# vcf.net
KiCad netlist of a schematic drawn in EAGLE
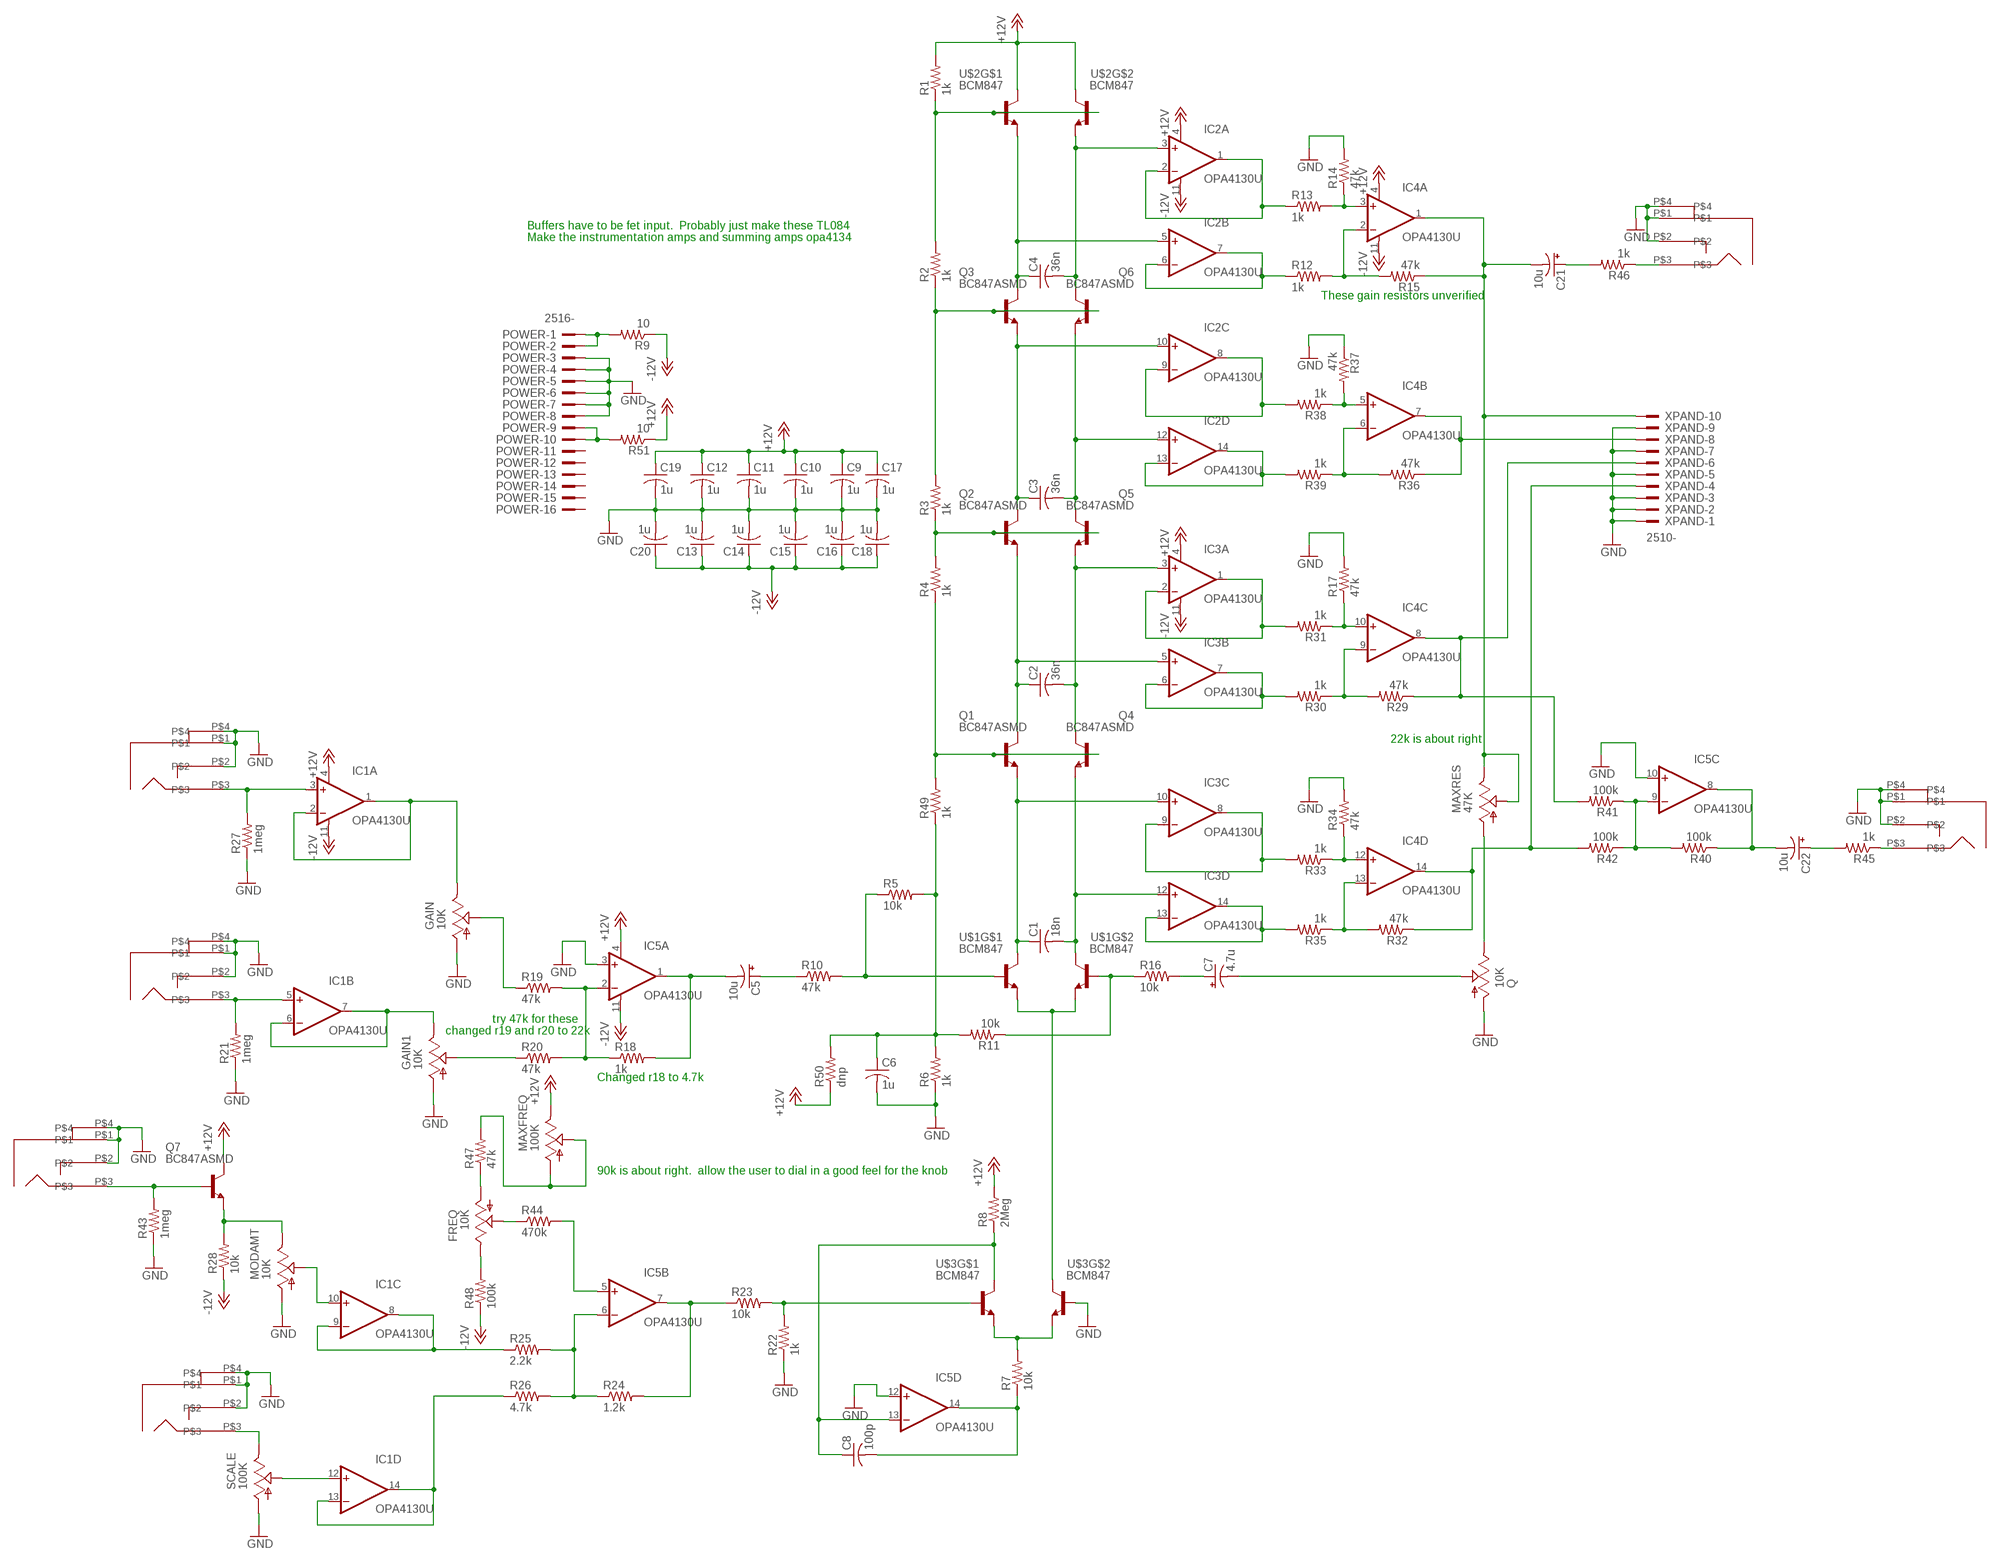
[diagram p0: schematic, sheet 1]

(export (version "E")
  (design (tool "Eeschema 10.0.6"))
  (components
    (comp (ref "AIN")
      (value "PJ301BM")
      (footprint "eagle-import:PJ301BM")
      (libsource (lib "eagle-import") (part "PJ301BM"))
    )
    (comp (ref "AIN2")
      (value "PJ301BM")
      (footprint "eagle-import:PJ301BM")
      (libsource (lib "eagle-import") (part "PJ301BM"))
    )
    (comp (ref "BP")
      (value "PJ301BM")
      (footprint "eagle-import:PJ301BM")
      (libsource (lib "eagle-import") (part "PJ301BM"))
    )
    (comp (ref "C1")
      (value "18n")
      (footprint "eagle-import:C0603")
      (libsource (lib "eagle-import") (part "C-USC0603"))
    )
    (comp (ref "C2")
      (value "36n")
      (footprint "eagle-import:C0603")
      (libsource (lib "eagle-import") (part "C-USC0603"))
    )
    (comp (ref "C3")
      (value "36n")
      (footprint "eagle-import:C0603")
      (libsource (lib "eagle-import") (part "C-USC0603"))
    )
    (comp (ref "C4")
      (value "36n")
      (footprint "eagle-import:C0603")
      (libsource (lib "eagle-import") (part "C-USC0603"))
    )
    (comp (ref "C5")
      (value "10u")
      (footprint "eagle-import:E2,5-6")
      (libsource (lib "eagle-import") (part "CPOL-USE2.5-6"))
    )
    (comp (ref "C6")
      (value "1u")
      (footprint "eagle-import:C0603")
      (libsource (lib "eagle-import") (part "C-USC0603"))
    )
    (comp (ref "C7")
      (value "4.7u")
      (footprint "eagle-import:E2,5-6")
      (libsource (lib "eagle-import") (part "CPOL-USE2.5-6"))
    )
    (comp (ref "C8")
      (value "100p")
      (footprint "eagle-import:C0603")
      (libsource (lib "eagle-import") (part "C-USC0603"))
    )
    (comp (ref "C9")
      (value "1u")
      (footprint "eagle-import:C0603")
      (libsource (lib "eagle-import") (part "C-USC0603"))
    )
    (comp (ref "C10")
      (value "1u")
      (footprint "eagle-import:C0603")
      (libsource (lib "eagle-import") (part "C-USC0603"))
    )
    (comp (ref "C11")
      (value "1u")
      (footprint "eagle-import:C0603")
      (libsource (lib "eagle-import") (part "C-USC0603"))
    )
    (comp (ref "C12")
      (value "1u")
      (footprint "eagle-import:C0603")
      (libsource (lib "eagle-import") (part "C-USC0603"))
    )
    (comp (ref "C13")
      (value "1u")
      (footprint "eagle-import:C0603")
      (libsource (lib "eagle-import") (part "C-USC0603"))
    )
    (comp (ref "C14")
      (value "1u")
      (footprint "eagle-import:C0603")
      (libsource (lib "eagle-import") (part "C-USC0603"))
    )
    (comp (ref "C15")
      (value "1u")
      (footprint "eagle-import:C0603")
      (libsource (lib "eagle-import") (part "C-USC0603"))
    )
    (comp (ref "C16")
      (value "1u")
      (footprint "eagle-import:C0603")
      (libsource (lib "eagle-import") (part "C-USC0603"))
    )
    (comp (ref "C17")
      (value "1u")
      (footprint "eagle-import:C0603")
      (libsource (lib "eagle-import") (part "C-USC0603"))
    )
    (comp (ref "C18")
      (value "1u")
      (footprint "eagle-import:C0603")
      (libsource (lib "eagle-import") (part "C-USC0603"))
    )
    (comp (ref "C19")
      (value "1u")
      (footprint "eagle-import:C0603")
      (libsource (lib "eagle-import") (part "C-USC0603"))
    )
    (comp (ref "C20")
      (value "1u")
      (footprint "eagle-import:C0603")
      (libsource (lib "eagle-import") (part "C-USC0603"))
    )
    (comp (ref "C21")
      (value "10u")
      (footprint "eagle-import:E2,5-6")
      (libsource (lib "eagle-import") (part "CPOL-USE2.5-6"))
    )
    (comp (ref "C22")
      (value "10u")
      (footprint "eagle-import:E2,5-6")
      (libsource (lib "eagle-import") (part "CPOL-USE2.5-6"))
    )
    (comp (ref "FREQ")
      (value "10K")
      (footprint "eagle-import:EVUFXJ")
      (libsource (lib "eagle-import") (part "US-EVUF2J"))
    )
    (comp (ref "GAIN")
      (value "10K")
      (footprint "eagle-import:EVUFXJ")
      (libsource (lib "eagle-import") (part "US-EVUF2J"))
    )
    (comp (ref "GAIN1")
      (value "10K")
      (footprint "eagle-import:EVUFXJ")
      (libsource (lib "eagle-import") (part "US-EVUF2J"))
    )
    (comp (ref "IC1")
      (value "OPA4130U")
      (footprint "eagle-import:SO14")
      (fields (field (name "MF") "TEXAS INSTRUMENTS") (field (name "MPN") "OPA4130UA"))
      (libsource (lib "eagle-import") (part "OPA4130U"))
    )
    (comp (ref "IC2")
      (value "OPA4130U")
      (footprint "eagle-import:SO14")
      (fields (field (name "MF") "TEXAS INSTRUMENTS") (field (name "MPN") "OPA4130UA"))
      (libsource (lib "eagle-import") (part "OPA4130U"))
    )
    (comp (ref "IC3")
      (value "OPA4130U")
      (footprint "eagle-import:SO14")
      (fields (field (name "MF") "TEXAS INSTRUMENTS") (field (name "MPN") "OPA4130UA"))
      (libsource (lib "eagle-import") (part "OPA4130U"))
    )
    (comp (ref "IC4")
      (value "OPA4130U")
      (footprint "eagle-import:SO14")
      (fields (field (name "MF") "TEXAS INSTRUMENTS") (field (name "MPN") "OPA4130UA"))
      (libsource (lib "eagle-import") (part "OPA4130U"))
    )
    (comp (ref "IC5")
      (value "OPA4130U")
      (footprint "eagle-import:SO14")
      (fields (field (name "MF") "TEXAS INSTRUMENTS") (field (name "MPN") "OPA4130UA"))
      (libsource (lib "eagle-import") (part "OPA4130U"))
    )
    (comp (ref "LP")
      (value "PJ301BM")
      (footprint "eagle-import:PJ301BM")
      (libsource (lib "eagle-import") (part "PJ301BM"))
    )
    (comp (ref "MAXFREQ")
      (value "100K")
      (footprint "eagle-import:S64W")
      (libsource (lib "eagle-import") (part "TRIM_US-S64W"))
    )
    (comp (ref "MAXRES")
      (value "47K")
      (footprint "eagle-import:S64W")
      (libsource (lib "eagle-import") (part "TRIM_US-S64W"))
    )
    (comp (ref "MIN")
      (value "PJ301BM")
      (footprint "eagle-import:PJ301BM")
      (libsource (lib "eagle-import") (part "PJ301BM"))
    )
    (comp (ref "MODAMT")
      (value "10K")
      (footprint "eagle-import:EVUFXJ")
      (libsource (lib "eagle-import") (part "US-EVUF2J"))
    )
    (comp (ref "POWER")
      (value "2516-")
      (footprint "eagle-import:PAK100_2500-16")
      (libsource (lib "eagle-import") (part "2516-"))
    )
    (comp (ref "Q")
      (value "10K")
      (footprint "eagle-import:EVUFXJ")
      (libsource (lib "eagle-import") (part "US-EVUF2J"))
    )
    (comp (ref "Q1")
      (value "BC847ASMD")
      (footprint "eagle-import:SOT23")
      (libsource (lib "eagle-import") (part "BC847SMDA"))
    )
    (comp (ref "Q2")
      (value "BC847ASMD")
      (footprint "eagle-import:SOT23")
      (libsource (lib "eagle-import") (part "BC847SMDA"))
    )
    (comp (ref "Q3")
      (value "BC847ASMD")
      (footprint "eagle-import:SOT23")
      (libsource (lib "eagle-import") (part "BC847SMDA"))
    )
    (comp (ref "Q4")
      (value "BC847ASMD")
      (footprint "eagle-import:SOT23")
      (libsource (lib "eagle-import") (part "BC847SMDA"))
    )
    (comp (ref "Q5")
      (value "BC847ASMD")
      (footprint "eagle-import:SOT23")
      (libsource (lib "eagle-import") (part "BC847SMDA"))
    )
    (comp (ref "Q6")
      (value "BC847ASMD")
      (footprint "eagle-import:SOT23")
      (libsource (lib "eagle-import") (part "BC847SMDA"))
    )
    (comp (ref "Q7")
      (value "BC847ASMD")
      (footprint "eagle-import:SOT23")
      (libsource (lib "eagle-import") (part "BC847SMDA"))
    )
    (comp (ref "R1")
      (value "1k")
      (footprint "eagle-import:R0603")
      (libsource (lib "eagle-import") (part "R-US_R0603"))
    )
    (comp (ref "R2")
      (value "1k")
      (footprint "eagle-import:R0603")
      (libsource (lib "eagle-import") (part "R-US_R0603"))
    )
    (comp (ref "R3")
      (value "1k")
      (footprint "eagle-import:R0603")
      (libsource (lib "eagle-import") (part "R-US_R0603"))
    )
    (comp (ref "R4")
      (value "1k")
      (footprint "eagle-import:R0603")
      (libsource (lib "eagle-import") (part "R-US_R0603"))
    )
    (comp (ref "R5")
      (value "10k")
      (footprint "eagle-import:R0603")
      (libsource (lib "eagle-import") (part "R-US_R0603"))
    )
    (comp (ref "R6")
      (value "1k")
      (footprint "eagle-import:R0603")
      (libsource (lib "eagle-import") (part "R-US_R0603"))
    )
    (comp (ref "R7")
      (value "10k")
      (footprint "eagle-import:R0603")
      (libsource (lib "eagle-import") (part "R-US_R0603"))
    )
    (comp (ref "R8")
      (value "2Meg")
      (footprint "eagle-import:R0603")
      (libsource (lib "eagle-import") (part "R-US_R0603"))
    )
    (comp (ref "R9")
      (value "10")
      (footprint "eagle-import:R0603")
      (libsource (lib "eagle-import") (part "R-US_R0603"))
    )
    (comp (ref "R10")
      (value "47k")
      (footprint "eagle-import:R0603")
      (libsource (lib "eagle-import") (part "R-US_R0603"))
    )
    (comp (ref "R11")
      (value "10k")
      (footprint "eagle-import:R0603")
      (libsource (lib "eagle-import") (part "R-US_R0603"))
    )
    (comp (ref "R12")
      (value "1k")
      (footprint "eagle-import:R0603")
      (libsource (lib "eagle-import") (part "R-US_R0603"))
    )
    (comp (ref "R13")
      (value "1k")
      (footprint "eagle-import:R0603")
      (libsource (lib "eagle-import") (part "R-US_R0603"))
    )
    (comp (ref "R14")
      (value "47k")
      (footprint "eagle-import:R0603")
      (libsource (lib "eagle-import") (part "R-US_R0603"))
    )
    (comp (ref "R15")
      (value "47k")
      (footprint "eagle-import:R0603")
      (libsource (lib "eagle-import") (part "R-US_R0603"))
    )
    (comp (ref "R16")
      (value "10k")
      (footprint "eagle-import:R0603")
      (libsource (lib "eagle-import") (part "R-US_R0603"))
    )
    (comp (ref "R17")
      (value "47k")
      (footprint "eagle-import:R0603")
      (libsource (lib "eagle-import") (part "R-US_R0603"))
    )
    (comp (ref "R18")
      (value "1k")
      (footprint "eagle-import:R0603")
      (libsource (lib "eagle-import") (part "R-US_R0603"))
    )
    (comp (ref "R19")
      (value "47k")
      (footprint "eagle-import:R0603")
      (libsource (lib "eagle-import") (part "R-US_R0603"))
    )
    (comp (ref "R20")
      (value "47k")
      (footprint "eagle-import:R0603")
      (libsource (lib "eagle-import") (part "R-US_R0603"))
    )
    (comp (ref "R21")
      (value "1meg")
      (footprint "eagle-import:R0603")
      (libsource (lib "eagle-import") (part "R-US_R0603"))
    )
    (comp (ref "R22")
      (value "1k")
      (footprint "eagle-import:R0603")
      (libsource (lib "eagle-import") (part "R-US_R0603"))
    )
    (comp (ref "R23")
      (value "10k")
      (footprint "eagle-import:R0603")
      (libsource (lib "eagle-import") (part "R-US_R0603"))
    )
    (comp (ref "R24")
      (value "1.2k")
      (footprint "eagle-import:R0603")
      (libsource (lib "eagle-import") (part "R-US_R0603"))
    )
    (comp (ref "R25")
      (value "2.2k")
      (footprint "eagle-import:R0603")
      (libsource (lib "eagle-import") (part "R-US_R0603"))
    )
    (comp (ref "R26")
      (value "4.7k")
      (footprint "eagle-import:R0603")
      (libsource (lib "eagle-import") (part "R-US_R0603"))
    )
    (comp (ref "R27")
      (value "1meg")
      (footprint "eagle-import:R0603")
      (libsource (lib "eagle-import") (part "R-US_R0603"))
    )
    (comp (ref "R28")
      (value "10k")
      (footprint "eagle-import:R0603")
      (libsource (lib "eagle-import") (part "R-US_R0603"))
    )
    (comp (ref "R29")
      (value "47k")
      (footprint "eagle-import:R0603")
      (libsource (lib "eagle-import") (part "R-US_R0603"))
    )
    (comp (ref "R30")
      (value "1k")
      (footprint "eagle-import:R0603")
      (libsource (lib "eagle-import") (part "R-US_R0603"))
    )
    (comp (ref "R31")
      (value "1k")
      (footprint "eagle-import:R0603")
      (libsource (lib "eagle-import") (part "R-US_R0603"))
    )
    (comp (ref "R32")
      (value "47k")
      (footprint "eagle-import:R0603")
      (libsource (lib "eagle-import") (part "R-US_R0603"))
    )
    (comp (ref "R33")
      (value "1k")
      (footprint "eagle-import:R0603")
      (libsource (lib "eagle-import") (part "R-US_R0603"))
    )
    (comp (ref "R34")
      (value "47k")
      (footprint "eagle-import:R0603")
      (libsource (lib "eagle-import") (part "R-US_R0603"))
    )
    (comp (ref "R35")
      (value "1k")
      (footprint "eagle-import:R0603")
      (libsource (lib "eagle-import") (part "R-US_R0603"))
    )
    (comp (ref "R36")
      (value "47k")
      (footprint "eagle-import:R0603")
      (libsource (lib "eagle-import") (part "R-US_R0603"))
    )
    (comp (ref "R37")
      (value "47k")
      (footprint "eagle-import:R0603")
      (libsource (lib "eagle-import") (part "R-US_R0603"))
    )
    (comp (ref "R38")
      (value "1k")
      (footprint "eagle-import:R0603")
      (libsource (lib "eagle-import") (part "R-US_R0603"))
    )
    (comp (ref "R39")
      (value "1k")
      (footprint "eagle-import:R0603")
      (libsource (lib "eagle-import") (part "R-US_R0603"))
    )
    (comp (ref "R40")
      (value "100k")
      (footprint "eagle-import:R0603")
      (libsource (lib "eagle-import") (part "R-US_R0603"))
    )
    (comp (ref "R41")
      (value "100k")
      (footprint "eagle-import:R0603")
      (libsource (lib "eagle-import") (part "R-US_R0603"))
    )
    (comp (ref "R42")
      (value "100k")
      (footprint "eagle-import:R0603")
      (libsource (lib "eagle-import") (part "R-US_R0603"))
    )
    (comp (ref "R43")
      (value "1meg")
      (footprint "eagle-import:R0603")
      (libsource (lib "eagle-import") (part "R-US_R0603"))
    )
    (comp (ref "R44")
      (value "470k")
      (footprint "eagle-import:R0603")
      (libsource (lib "eagle-import") (part "R-US_R0603"))
    )
    (comp (ref "R45")
      (value "1k")
      (footprint "eagle-import:R0603")
      (libsource (lib "eagle-import") (part "R-US_R0603"))
    )
    (comp (ref "R46")
      (value "1k")
      (footprint "eagle-import:R0603")
      (libsource (lib "eagle-import") (part "R-US_R0603"))
    )
    (comp (ref "R47")
      (value "47k")
      (footprint "eagle-import:R0603")
      (libsource (lib "eagle-import") (part "R-US_R0603"))
    )
    (comp (ref "R48")
      (value "100k")
      (footprint "eagle-import:R0603")
      (libsource (lib "eagle-import") (part "R-US_R0603"))
    )
    (comp (ref "R49")
      (value "1k")
      (footprint "eagle-import:R0603")
      (libsource (lib "eagle-import") (part "R-US_R0603"))
    )
    (comp (ref "R50")
      (value "dnp")
      (footprint "eagle-import:R0603")
      (libsource (lib "eagle-import") (part "R-US_R0603"))
    )
    (comp (ref "R51")
      (value "10")
      (footprint "eagle-import:R0603")
      (libsource (lib "eagle-import") (part "R-US_R0603"))
    )
    (comp (ref "SCALE")
      (value "100K")
      (footprint "eagle-import:S64W")
      (libsource (lib "eagle-import") (part "TRIM_US-S64W"))
    )
    (comp (ref "U$1")
      (value "BCM847")
      (footprint "eagle-import:SOT457R_PHILIPS")
      (libsource (lib "eagle-import") (part "BCM847"))
    )
    (comp (ref "U$2")
      (value "BCM847")
      (footprint "eagle-import:SOT457R_PHILIPS")
      (libsource (lib "eagle-import") (part "BCM847"))
    )
    (comp (ref "U$3")
      (value "BCM847")
      (footprint "eagle-import:SOT457R_PHILIPS")
      (libsource (lib "eagle-import") (part "BCM847"))
    )
    (comp (ref "VPEROCT")
      (value "PJ301BM")
      (footprint "eagle-import:PJ301BM")
      (libsource (lib "eagle-import") (part "PJ301BM"))
    )
    (comp (ref "XPAND")
      (value "2510-")
      (footprint "eagle-import:PAK100_2500-10")
      (fields (field (name "MF") "3M") (field (name "MPN") "2510-6002UB"))
      (libsource (lib "eagle-import") (part "2510-"))
    )
  )
  (nets
    (net (code "1") (name "+12V") (class "Default")
      (node (ref "C10") (pin "1") (pinfunction "1_1") (pintype "passive"))
      (node (ref "C11") (pin "1") (pinfunction "1_1") (pintype "passive"))
      (node (ref "C12") (pin "1") (pinfunction "1_1") (pintype "passive"))
      (node (ref "C17") (pin "1") (pinfunction "1_1") (pintype "passive"))
      (node (ref "C19") (pin "1") (pinfunction "1_1") (pintype "passive"))
      (node (ref "C9") (pin "1") (pinfunction "1_1") (pintype "passive"))
      (node (ref "IC1") (pin "4") (pinfunction "V+_4") (pintype "power_in"))
      (node (ref "IC2") (pin "4") (pinfunction "V+_4") (pintype "power_in"))
      (node (ref "IC3") (pin "4") (pinfunction "V+_4") (pintype "power_in"))
      (node (ref "IC4") (pin "4") (pinfunction "V+_4") (pintype "power_in"))
      (node (ref "IC5") (pin "4") (pinfunction "V+_4") (pintype "power_in"))
      (node (ref "MAXFREQ") (pin "E") (pinfunction "E_E") (pintype "passive"))
      (node (ref "Q7") (pin "3") (pinfunction "C_3") (pintype "passive"))
      (node (ref "R1") (pin "2") (pinfunction "2_2") (pintype "passive"))
      (node (ref "R50") (pin "1") (pinfunction "1_1") (pintype "passive"))
      (node (ref "R51") (pin "1") (pinfunction "1_1") (pintype "passive"))
      (node (ref "R8") (pin "2") (pinfunction "2_2") (pintype "passive"))
      (node (ref "U$2") (pin "3") (pinfunction "C_3") (pintype "passive"))
      (node (ref "U$2") (pin "6") (pinfunction "C_6") (pintype "passive"))
    )
    (net (code "2") (name "-12V") (class "Default")
      (node (ref "C13") (pin "1") (pinfunction "1_1") (pintype "passive"))
      (node (ref "C14") (pin "1") (pinfunction "1_1") (pintype "passive"))
      (node (ref "C15") (pin "1") (pinfunction "1_1") (pintype "passive"))
      (node (ref "C16") (pin "1") (pinfunction "1_1") (pintype "passive"))
      (node (ref "C18") (pin "1") (pinfunction "1_1") (pintype "passive"))
      (node (ref "C20") (pin "1") (pinfunction "1_1") (pintype "passive"))
      (node (ref "IC1") (pin "11") (pinfunction "V-_11") (pintype "power_in"))
      (node (ref "IC2") (pin "11") (pinfunction "V-_11") (pintype "power_in"))
      (node (ref "IC3") (pin "11") (pinfunction "V-_11") (pintype "power_in"))
      (node (ref "IC4") (pin "11") (pinfunction "V-_11") (pintype "power_in"))
      (node (ref "IC5") (pin "11") (pinfunction "V-_11") (pintype "power_in"))
      (node (ref "R28") (pin "1") (pinfunction "1_1") (pintype "passive"))
      (node (ref "R48") (pin "1") (pinfunction "1_1") (pintype "passive"))
      (node (ref "R9") (pin "1") (pinfunction "1_1") (pintype "passive"))
    )
    (net (code "3") (name "GND") (class "Default")
      (node (ref "AIN") (pin "P$1") (pinfunction "P$1_P$1") (pintype "bidirectional"))
      (node (ref "AIN") (pin "P$2") (pinfunction "P$2_P$2") (pintype "bidirectional"))
      (node (ref "AIN") (pin "P$4") (pinfunction "P$4_P$4") (pintype "bidirectional"))
      (node (ref "AIN2") (pin "P$1") (pinfunction "P$1_P$1") (pintype "bidirectional"))
      (node (ref "AIN2") (pin "P$2") (pinfunction "P$2_P$2") (pintype "bidirectional"))
      (node (ref "AIN2") (pin "P$4") (pinfunction "P$4_P$4") (pintype "bidirectional"))
      (node (ref "BP") (pin "P$1") (pinfunction "P$1_P$1") (pintype "bidirectional"))
      (node (ref "BP") (pin "P$2") (pinfunction "P$2_P$2") (pintype "bidirectional"))
      (node (ref "BP") (pin "P$4") (pinfunction "P$4_P$4") (pintype "bidirectional"))
      (node (ref "C10") (pin "2") (pinfunction "2_2") (pintype "passive"))
      (node (ref "C11") (pin "2") (pinfunction "2_2") (pintype "passive"))
      (node (ref "C12") (pin "2") (pinfunction "2_2") (pintype "passive"))
      (node (ref "C13") (pin "2") (pinfunction "2_2") (pintype "passive"))
      (node (ref "C14") (pin "2") (pinfunction "2_2") (pintype "passive"))
      (node (ref "C15") (pin "2") (pinfunction "2_2") (pintype "passive"))
      (node (ref "C16") (pin "2") (pinfunction "2_2") (pintype "passive"))
      (node (ref "C17") (pin "2") (pinfunction "2_2") (pintype "passive"))
      (node (ref "C18") (pin "2") (pinfunction "2_2") (pintype "passive"))
      (node (ref "C19") (pin "2") (pinfunction "2_2") (pintype "passive"))
      (node (ref "C20") (pin "2") (pinfunction "2_2") (pintype "passive"))
      (node (ref "C6") (pin "2") (pinfunction "2_2") (pintype "passive"))
      (node (ref "C9") (pin "2") (pinfunction "2_2") (pintype "passive"))
      (node (ref "GAIN") (pin "1") (pinfunction "A_1") (pintype "passive"))
      (node (ref "GAIN1") (pin "1") (pinfunction "A_1") (pintype "passive"))
      (node (ref "IC5") (pin "10") (pinfunction "+IN_10") (pintype "input"))
      (node (ref "IC5") (pin "12") (pinfunction "+IN_12") (pintype "input"))
      (node (ref "IC5") (pin "3") (pinfunction "+IN_3") (pintype "input"))
      (node (ref "LP") (pin "P$1") (pinfunction "P$1_P$1") (pintype "bidirectional"))
      (node (ref "LP") (pin "P$2") (pinfunction "P$2_P$2") (pintype "bidirectional"))
      (node (ref "LP") (pin "P$4") (pinfunction "P$4_P$4") (pintype "bidirectional"))
      (node (ref "MIN") (pin "P$1") (pinfunction "P$1_P$1") (pintype "bidirectional"))
      (node (ref "MIN") (pin "P$2") (pinfunction "P$2_P$2") (pintype "bidirectional"))
      (node (ref "MIN") (pin "P$4") (pinfunction "P$4_P$4") (pintype "bidirectional"))
      (node (ref "MODAMT") (pin "1") (pinfunction "A_1") (pintype "passive"))
      (node (ref "POWER") (pin "3") (pinfunction "KL_3") (pintype "passive"))
      (node (ref "POWER") (pin "4") (pinfunction "KL_4") (pintype "passive"))
      (node (ref "POWER") (pin "5") (pinfunction "KL_5") (pintype "passive"))
      (node (ref "POWER") (pin "6") (pinfunction "KL_6") (pintype "passive"))
      (node (ref "POWER") (pin "7") (pinfunction "KL_7") (pintype "passive"))
      (node (ref "POWER") (pin "8") (pinfunction "KL_8") (pintype "passive"))
      (node (ref "Q") (pin "1") (pinfunction "A_1") (pintype "passive"))
      (node (ref "R14") (pin "2") (pinfunction "2_2") (pintype "passive"))
      (node (ref "R17") (pin "2") (pinfunction "2_2") (pintype "passive"))
      (node (ref "R21") (pin "1") (pinfunction "1_1") (pintype "passive"))
      (node (ref "R22") (pin "1") (pinfunction "1_1") (pintype "passive"))
      (node (ref "R27") (pin "1") (pinfunction "1_1") (pintype "passive"))
      (node (ref "R34") (pin "2") (pinfunction "2_2") (pintype "passive"))
      (node (ref "R37") (pin "1") (pinfunction "1_1") (pintype "passive"))
      (node (ref "R43") (pin "1") (pinfunction "1_1") (pintype "passive"))
      (node (ref "R6") (pin "1") (pinfunction "1_1") (pintype "passive"))
      (node (ref "SCALE") (pin "A") (pinfunction "A_A") (pintype "passive"))
      (node (ref "U$3") (pin "5") (pinfunction "B_5") (pintype "passive"))
      (node (ref "VPEROCT") (pin "P$1") (pinfunction "P$1_P$1") (pintype "bidirectional"))
      (node (ref "VPEROCT") (pin "P$2") (pinfunction "P$2_P$2") (pintype "bidirectional"))
      (node (ref "VPEROCT") (pin "P$4") (pinfunction "P$4_P$4") (pintype "bidirectional"))
      (node (ref "XPAND") (pin "1") (pinfunction "KL_1") (pintype "passive"))
      (node (ref "XPAND") (pin "2") (pinfunction "KL_2") (pintype "passive"))
      (node (ref "XPAND") (pin "3") (pinfunction "KL_3") (pintype "passive"))
      (node (ref "XPAND") (pin "5") (pinfunction "KL_5") (pintype "passive"))
      (node (ref "XPAND") (pin "7") (pinfunction "KL_7") (pintype "passive"))
      (node (ref "XPAND") (pin "9") (pinfunction "KL_9") (pintype "passive"))
    )
    (net (code "4") (name "Net-(BP-PadP$3)") (class "Default")
      (node (ref "BP") (pin "P$3") (pinfunction "P$3_P$3") (pintype "bidirectional"))
      (node (ref "R45") (pin "1") (pinfunction "1_1") (pintype "passive"))
    )
    (net (code "5") (name "Net-(C5-Pad+)") (class "Default")
      (node (ref "C5") (pin "+") (pinfunction "+_+") (pintype "passive"))
      (node (ref "R10") (pin "1") (pinfunction "1_1") (pintype "passive"))
    )
    (net (code "6") (name "Net-(C6-Pad1)") (class "Default")
      (node (ref "C6") (pin "1") (pinfunction "1_1") (pintype "passive"))
      (node (ref "R11") (pin "2") (pinfunction "2_2") (pintype "passive"))
      (node (ref "R49") (pin "1") (pinfunction "1_1") (pintype "passive"))
      (node (ref "R5") (pin "2") (pinfunction "2_2") (pintype "passive"))
      (node (ref "R50") (pin "2") (pinfunction "2_2") (pintype "passive"))
      (node (ref "R6") (pin "2") (pinfunction "2_2") (pintype "passive"))
    )
    (net (code "7") (name "Net-(C7-Pad+)") (class "Default")
      (node (ref "C7") (pin "+") (pinfunction "+_+") (pintype "passive"))
      (node (ref "R16") (pin "2") (pinfunction "2_2") (pintype "passive"))
    )
    (net (code "8") (name "Net-(C21-Pad+)") (class "Default")
      (node (ref "C21") (pin "+") (pinfunction "+_+") (pintype "passive"))
      (node (ref "R46") (pin "2") (pinfunction "2_2") (pintype "passive"))
    )
    (net (code "9") (name "Net-(C22-Pad+)") (class "Default")
      (node (ref "C22") (pin "+") (pinfunction "+_+") (pintype "passive"))
      (node (ref "R45") (pin "2") (pinfunction "2_2") (pintype "passive"))
    )
    (net (code "10") (name "Net-(FREQ-A)") (class "Default")
      (node (ref "FREQ") (pin "1") (pinfunction "A_1") (pintype "passive"))
      (node (ref "R47") (pin "1") (pinfunction "1_1") (pintype "passive"))
    )
    (net (code "11") (name "Net-(FREQ-E)") (class "Default")
      (node (ref "FREQ") (pin "3") (pinfunction "E_3") (pintype "passive"))
      (node (ref "R48") (pin "2") (pinfunction "2_2") (pintype "passive"))
    )
    (net (code "12") (name "Net-(FREQ-S)") (class "Default")
      (node (ref "FREQ") (pin "2") (pinfunction "S_2") (pintype "passive"))
      (node (ref "R44") (pin "1") (pinfunction "1_1") (pintype "passive"))
    )
    (net (code "13") (name "Net-(GAIN-E)") (class "Default")
      (node (ref "GAIN") (pin "3") (pinfunction "E_3") (pintype "passive"))
      (node (ref "IC1") (pin "1") (pinfunction "OUT_1") (pintype "output"))
      (node (ref "IC1") (pin "2") (pinfunction "-IN_2") (pintype "input"))
    )
    (net (code "14") (name "Net-(GAIN-S)") (class "Default")
      (node (ref "GAIN") (pin "2") (pinfunction "S_2") (pintype "passive"))
      (node (ref "R19") (pin "1") (pinfunction "1_1") (pintype "passive"))
    )
    (net (code "15") (name "Net-(GAIN1-E)") (class "Default")
      (node (ref "GAIN1") (pin "3") (pinfunction "E_3") (pintype "passive"))
      (node (ref "IC1") (pin "6") (pinfunction "-IN_6") (pintype "input"))
      (node (ref "IC1") (pin "7") (pinfunction "OUT_7") (pintype "output"))
    )
    (net (code "16") (name "Net-(GAIN1-S)") (class "Default")
      (node (ref "GAIN1") (pin "2") (pinfunction "S_2") (pintype "passive"))
      (node (ref "R20") (pin "1") (pinfunction "1_1") (pintype "passive"))
    )
    (net (code "17") (name "Net-(IC1A-+IN)") (class "Default")
      (node (ref "AIN") (pin "P$3") (pinfunction "P$3_P$3") (pintype "bidirectional"))
      (node (ref "IC1") (pin "3") (pinfunction "+IN_3") (pintype "input"))
      (node (ref "R27") (pin "2") (pinfunction "2_2") (pintype "passive"))
    )
    (net (code "18") (name "Net-(IC1B-+IN)") (class "Default")
      (node (ref "AIN2") (pin "P$3") (pinfunction "P$3_P$3") (pintype "bidirectional"))
      (node (ref "IC1") (pin "5") (pinfunction "+IN_5") (pintype "input"))
      (node (ref "R21") (pin "2") (pinfunction "2_2") (pintype "passive"))
    )
    (net (code "19") (name "Net-(IC1C-+IN)") (class "Default")
      (node (ref "IC1") (pin "10") (pinfunction "+IN_10") (pintype "input"))
      (node (ref "MODAMT") (pin "2") (pinfunction "S_2") (pintype "passive"))
    )
    (net (code "20") (name "Net-(IC1C--IN)") (class "Default")
      (node (ref "IC1") (pin "8") (pinfunction "OUT_8") (pintype "output"))
      (node (ref "IC1") (pin "9") (pinfunction "-IN_9") (pintype "input"))
      (node (ref "R25") (pin "1") (pinfunction "1_1") (pintype "passive"))
    )
    (net (code "21") (name "Net-(IC1D-+IN)") (class "Default")
      (node (ref "IC1") (pin "12") (pinfunction "+IN_12") (pintype "input"))
      (node (ref "SCALE") (pin "S") (pinfunction "S_S") (pintype "passive"))
    )
    (net (code "22") (name "Net-(IC1D--IN)") (class "Default")
      (node (ref "IC1") (pin "13") (pinfunction "-IN_13") (pintype "input"))
      (node (ref "IC1") (pin "14") (pinfunction "OUT_14") (pintype "output"))
      (node (ref "R26") (pin "1") (pinfunction "1_1") (pintype "passive"))
    )
    (net (code "23") (name "Net-(IC2A-+IN)") (class "Default")
      (node (ref "C4") (pin "2") (pinfunction "2_2") (pintype "passive"))
      (node (ref "IC2") (pin "3") (pinfunction "+IN_3") (pintype "input"))
      (node (ref "Q6") (pin "3") (pinfunction "C_3") (pintype "passive"))
      (node (ref "U$2") (pin "4") (pinfunction "E_4") (pintype "passive"))
    )
    (net (code "24") (name "Net-(IC2A--IN)") (class "Default")
      (node (ref "IC2") (pin "1") (pinfunction "OUT_1") (pintype "output"))
      (node (ref "IC2") (pin "2") (pinfunction "-IN_2") (pintype "input"))
      (node (ref "R13") (pin "1") (pinfunction "1_1") (pintype "passive"))
    )
    (net (code "25") (name "Net-(IC2B-+IN)") (class "Default")
      (node (ref "C4") (pin "1") (pinfunction "1_1") (pintype "passive"))
      (node (ref "IC2") (pin "5") (pinfunction "+IN_5") (pintype "input"))
      (node (ref "Q3") (pin "3") (pinfunction "C_3") (pintype "passive"))
      (node (ref "U$2") (pin "1") (pinfunction "E_1") (pintype "passive"))
    )
    (net (code "26") (name "Net-(IC2B--IN)") (class "Default")
      (node (ref "IC2") (pin "6") (pinfunction "-IN_6") (pintype "input"))
      (node (ref "IC2") (pin "7") (pinfunction "OUT_7") (pintype "output"))
      (node (ref "R12") (pin "1") (pinfunction "1_1") (pintype "passive"))
    )
    (net (code "27") (name "Net-(IC2C-+IN)") (class "Default")
      (node (ref "C3") (pin "1") (pinfunction "1_1") (pintype "passive"))
      (node (ref "IC2") (pin "10") (pinfunction "+IN_10") (pintype "input"))
      (node (ref "Q2") (pin "3") (pinfunction "C_3") (pintype "passive"))
      (node (ref "Q3") (pin "2") (pinfunction "E_2") (pintype "passive"))
    )
    (net (code "28") (name "Net-(IC2C--IN)") (class "Default")
      (node (ref "IC2") (pin "8") (pinfunction "OUT_8") (pintype "output"))
      (node (ref "IC2") (pin "9") (pinfunction "-IN_9") (pintype "input"))
      (node (ref "R38") (pin "2") (pinfunction "2_2") (pintype "passive"))
    )
    (net (code "29") (name "Net-(IC2D-+IN)") (class "Default")
      (node (ref "C3") (pin "2") (pinfunction "2_2") (pintype "passive"))
      (node (ref "IC2") (pin "12") (pinfunction "+IN_12") (pintype "input"))
      (node (ref "Q5") (pin "3") (pinfunction "C_3") (pintype "passive"))
      (node (ref "Q6") (pin "2") (pinfunction "E_2") (pintype "passive"))
    )
    (net (code "30") (name "Net-(IC2D--IN)") (class "Default")
      (node (ref "IC2") (pin "13") (pinfunction "-IN_13") (pintype "input"))
      (node (ref "IC2") (pin "14") (pinfunction "OUT_14") (pintype "output"))
      (node (ref "R39") (pin "2") (pinfunction "2_2") (pintype "passive"))
    )
    (net (code "31") (name "Net-(IC3A-+IN)") (class "Default")
      (node (ref "C2") (pin "2") (pinfunction "2_2") (pintype "passive"))
      (node (ref "IC3") (pin "3") (pinfunction "+IN_3") (pintype "input"))
      (node (ref "Q4") (pin "3") (pinfunction "C_3") (pintype "passive"))
      (node (ref "Q5") (pin "2") (pinfunction "E_2") (pintype "passive"))
    )
    (net (code "32") (name "Net-(IC3A--IN)") (class "Default")
      (node (ref "IC3") (pin "1") (pinfunction "OUT_1") (pintype "output"))
      (node (ref "IC3") (pin "2") (pinfunction "-IN_2") (pintype "input"))
      (node (ref "R31") (pin "2") (pinfunction "2_2") (pintype "passive"))
    )
    (net (code "33") (name "Net-(IC3B-+IN)") (class "Default")
      (node (ref "C2") (pin "1") (pinfunction "1_1") (pintype "passive"))
      (node (ref "IC3") (pin "5") (pinfunction "+IN_5") (pintype "input"))
      (node (ref "Q1") (pin "3") (pinfunction "C_3") (pintype "passive"))
      (node (ref "Q2") (pin "2") (pinfunction "E_2") (pintype "passive"))
    )
    (net (code "34") (name "Net-(IC3B--IN)") (class "Default")
      (node (ref "IC3") (pin "6") (pinfunction "-IN_6") (pintype "input"))
      (node (ref "IC3") (pin "7") (pinfunction "OUT_7") (pintype "output"))
      (node (ref "R30") (pin "2") (pinfunction "2_2") (pintype "passive"))
    )
    (net (code "35") (name "Net-(IC3C-+IN)") (class "Default")
      (node (ref "C1") (pin "1") (pinfunction "1_1") (pintype "passive"))
      (node (ref "IC3") (pin "10") (pinfunction "+IN_10") (pintype "input"))
      (node (ref "Q1") (pin "2") (pinfunction "E_2") (pintype "passive"))
      (node (ref "U$1") (pin "6") (pinfunction "C_6") (pintype "passive"))
    )
    (net (code "36") (name "Net-(IC3C--IN)") (class "Default")
      (node (ref "IC3") (pin "8") (pinfunction "OUT_8") (pintype "output"))
      (node (ref "IC3") (pin "9") (pinfunction "-IN_9") (pintype "input"))
      (node (ref "R33") (pin "2") (pinfunction "2_2") (pintype "passive"))
    )
    (net (code "37") (name "Net-(IC3D-+IN)") (class "Default")
      (node (ref "C1") (pin "2") (pinfunction "2_2") (pintype "passive"))
      (node (ref "IC3") (pin "12") (pinfunction "+IN_12") (pintype "input"))
      (node (ref "Q4") (pin "2") (pinfunction "E_2") (pintype "passive"))
      (node (ref "U$1") (pin "3") (pinfunction "C_3") (pintype "passive"))
    )
    (net (code "38") (name "Net-(IC3D--IN)") (class "Default")
      (node (ref "IC3") (pin "13") (pinfunction "-IN_13") (pintype "input"))
      (node (ref "IC3") (pin "14") (pinfunction "OUT_14") (pintype "output"))
      (node (ref "R35") (pin "2") (pinfunction "2_2") (pintype "passive"))
    )
    (net (code "39") (name "Net-(IC4A-+IN)") (class "Default")
      (node (ref "IC4") (pin "3") (pinfunction "+IN_3") (pintype "input"))
      (node (ref "R13") (pin "2") (pinfunction "2_2") (pintype "passive"))
      (node (ref "R14") (pin "1") (pinfunction "1_1") (pintype "passive"))
    )
    (net (code "40") (name "Net-(IC4A--IN)") (class "Default")
      (node (ref "IC4") (pin "2") (pinfunction "-IN_2") (pintype "input"))
      (node (ref "R12") (pin "2") (pinfunction "2_2") (pintype "passive"))
      (node (ref "R15") (pin "2") (pinfunction "2_2") (pintype "passive"))
    )
    (net (code "41") (name "Net-(IC4A-OUT)") (class "Default")
      (node (ref "C21") (pin "-") (pinfunction "-_-") (pintype "passive"))
      (node (ref "IC4") (pin "1") (pinfunction "OUT_1") (pintype "output"))
      (node (ref "MAXRES") (pin "E") (pinfunction "E_E") (pintype "passive"))
      (node (ref "MAXRES") (pin "S") (pinfunction "S_S") (pintype "passive"))
      (node (ref "R15") (pin "1") (pinfunction "1_1") (pintype "passive"))
      (node (ref "XPAND") (pin "10") (pinfunction "KL_10") (pintype "passive"))
    )
    (net (code "42") (name "Net-(IC4B-+IN)") (class "Default")
      (node (ref "IC4") (pin "5") (pinfunction "+IN_5") (pintype "input"))
      (node (ref "R37") (pin "2") (pinfunction "2_2") (pintype "passive"))
      (node (ref "R38") (pin "1") (pinfunction "1_1") (pintype "passive"))
    )
    (net (code "43") (name "Net-(IC4B--IN)") (class "Default")
      (node (ref "IC4") (pin "6") (pinfunction "-IN_6") (pintype "input"))
      (node (ref "R36") (pin "2") (pinfunction "2_2") (pintype "passive"))
      (node (ref "R39") (pin "1") (pinfunction "1_1") (pintype "passive"))
    )
    (net (code "44") (name "Net-(IC4B-OUT)") (class "Default")
      (node (ref "IC4") (pin "7") (pinfunction "OUT_7") (pintype "output"))
      (node (ref "R36") (pin "1") (pinfunction "1_1") (pintype "passive"))
      (node (ref "XPAND") (pin "8") (pinfunction "KL_8") (pintype "passive"))
    )
    (net (code "45") (name "Net-(IC4C-+IN)") (class "Default")
      (node (ref "IC4") (pin "10") (pinfunction "+IN_10") (pintype "input"))
      (node (ref "R17") (pin "1") (pinfunction "1_1") (pintype "passive"))
      (node (ref "R31") (pin "1") (pinfunction "1_1") (pintype "passive"))
    )
    (net (code "46") (name "Net-(IC4C--IN)") (class "Default")
      (node (ref "IC4") (pin "9") (pinfunction "-IN_9") (pintype "input"))
      (node (ref "R29") (pin "2") (pinfunction "2_2") (pintype "passive"))
      (node (ref "R30") (pin "1") (pinfunction "1_1") (pintype "passive"))
    )
    (net (code "47") (name "Net-(IC4C-OUT)") (class "Default")
      (node (ref "IC4") (pin "8") (pinfunction "OUT_8") (pintype "output"))
      (node (ref "R29") (pin "1") (pinfunction "1_1") (pintype "passive"))
      (node (ref "R41") (pin "2") (pinfunction "2_2") (pintype "passive"))
      (node (ref "XPAND") (pin "6") (pinfunction "KL_6") (pintype "passive"))
    )
    (net (code "48") (name "Net-(IC4D-+IN)") (class "Default")
      (node (ref "IC4") (pin "12") (pinfunction "+IN_12") (pintype "input"))
      (node (ref "R33") (pin "1") (pinfunction "1_1") (pintype "passive"))
      (node (ref "R34") (pin "1") (pinfunction "1_1") (pintype "passive"))
    )
    (net (code "49") (name "Net-(IC4D--IN)") (class "Default")
      (node (ref "IC4") (pin "13") (pinfunction "-IN_13") (pintype "input"))
      (node (ref "R32") (pin "2") (pinfunction "2_2") (pintype "passive"))
      (node (ref "R35") (pin "1") (pinfunction "1_1") (pintype "passive"))
    )
    (net (code "50") (name "Net-(IC4D-OUT)") (class "Default")
      (node (ref "IC4") (pin "14") (pinfunction "OUT_14") (pintype "output"))
      (node (ref "R32") (pin "1") (pinfunction "1_1") (pintype "passive"))
      (node (ref "R42") (pin "2") (pinfunction "2_2") (pintype "passive"))
      (node (ref "XPAND") (pin "4") (pinfunction "KL_4") (pintype "passive"))
    )
    (net (code "51") (name "Net-(IC5A--IN)") (class "Default")
      (node (ref "IC5") (pin "2") (pinfunction "-IN_2") (pintype "input"))
      (node (ref "R18") (pin "1") (pinfunction "1_1") (pintype "passive"))
      (node (ref "R19") (pin "2") (pinfunction "2_2") (pintype "passive"))
      (node (ref "R20") (pin "2") (pinfunction "2_2") (pintype "passive"))
    )
    (net (code "52") (name "Net-(IC5A-OUT)") (class "Default")
      (node (ref "C5") (pin "-") (pinfunction "-_-") (pintype "passive"))
      (node (ref "IC5") (pin "1") (pinfunction "OUT_1") (pintype "output"))
      (node (ref "R18") (pin "2") (pinfunction "2_2") (pintype "passive"))
    )
    (net (code "53") (name "Net-(IC5B-+IN)") (class "Default")
      (node (ref "IC5") (pin "5") (pinfunction "+IN_5") (pintype "input"))
      (node (ref "R44") (pin "2") (pinfunction "2_2") (pintype "passive"))
    )
    (net (code "54") (name "Net-(IC5B--IN)") (class "Default")
      (node (ref "IC5") (pin "6") (pinfunction "-IN_6") (pintype "input"))
      (node (ref "R24") (pin "1") (pinfunction "1_1") (pintype "passive"))
      (node (ref "R25") (pin "2") (pinfunction "2_2") (pintype "passive"))
      (node (ref "R26") (pin "2") (pinfunction "2_2") (pintype "passive"))
    )
    (net (code "55") (name "Net-(IC5B-OUT)") (class "Default")
      (node (ref "IC5") (pin "7") (pinfunction "OUT_7") (pintype "output"))
      (node (ref "R23") (pin "1") (pinfunction "1_1") (pintype "passive"))
      (node (ref "R24") (pin "2") (pinfunction "2_2") (pintype "passive"))
    )
    (net (code "56") (name "Net-(IC5C--IN)") (class "Default")
      (node (ref "IC5") (pin "9") (pinfunction "-IN_9") (pintype "input"))
      (node (ref "R40") (pin "2") (pinfunction "2_2") (pintype "passive"))
      (node (ref "R41") (pin "1") (pinfunction "1_1") (pintype "passive"))
      (node (ref "R42") (pin "1") (pinfunction "1_1") (pintype "passive"))
    )
    (net (code "57") (name "Net-(IC5C-OUT)") (class "Default")
      (node (ref "C22") (pin "-") (pinfunction "-_-") (pintype "passive"))
      (node (ref "IC5") (pin "8") (pinfunction "OUT_8") (pintype "output"))
      (node (ref "R40") (pin "1") (pinfunction "1_1") (pintype "passive"))
    )
    (net (code "58") (name "Net-(IC5D--IN)") (class "Default")
      (node (ref "C8") (pin "1") (pinfunction "1_1") (pintype "passive"))
      (node (ref "IC5") (pin "13") (pinfunction "-IN_13") (pintype "input"))
      (node (ref "R8") (pin "1") (pinfunction "1_1") (pintype "passive"))
      (node (ref "U$3") (pin "6") (pinfunction "C_6") (pintype "passive"))
    )
    (net (code "59") (name "Net-(IC5D-OUT)") (class "Default")
      (node (ref "C8") (pin "2") (pinfunction "2_2") (pintype "passive"))
      (node (ref "IC5") (pin "14") (pinfunction "OUT_14") (pintype "output"))
      (node (ref "R7") (pin "1") (pinfunction "1_1") (pintype "passive"))
    )
    (net (code "60") (name "Net-(LP-PadP$3)") (class "Default")
      (node (ref "LP") (pin "P$3") (pinfunction "P$3_P$3") (pintype "bidirectional"))
      (node (ref "R46") (pin "1") (pinfunction "1_1") (pintype "passive"))
    )
    (net (code "61") (name "Net-(MAXFREQ-PadA)") (class "Default")
      (node (ref "MAXFREQ") (pin "A") (pinfunction "A_A") (pintype "passive"))
      (node (ref "MAXFREQ") (pin "S") (pinfunction "S_S") (pintype "passive"))
      (node (ref "R47") (pin "2") (pinfunction "2_2") (pintype "passive"))
    )
    (net (code "62") (name "Net-(MODAMT-E)") (class "Default")
      (node (ref "MODAMT") (pin "3") (pinfunction "E_3") (pintype "passive"))
      (node (ref "Q7") (pin "2") (pinfunction "E_2") (pintype "passive"))
      (node (ref "R28") (pin "2") (pinfunction "2_2") (pintype "passive"))
    )
    (net (code "63") (name "Net-(POWERA-KL)") (class "Default")
      (node (ref "POWER") (pin "1") (pinfunction "KL_1") (pintype "passive"))
      (node (ref "POWER") (pin "2") (pinfunction "KL_2") (pintype "passive"))
      (node (ref "R9") (pin "2") (pinfunction "2_2") (pintype "passive"))
    )
    (net (code "64") (name "Net-(POWERB-KL)") (class "Default")
      (node (ref "POWER") (pin "10") (pinfunction "KL_10") (pintype "passive"))
      (node (ref "POWER") (pin "9") (pinfunction "KL_9") (pintype "passive"))
      (node (ref "R51") (pin "2") (pinfunction "2_2") (pintype "passive"))
    )
    (net (code "65") (name "Net-(Q-E)") (class "Default")
      (node (ref "MAXRES") (pin "A") (pinfunction "A_A") (pintype "passive"))
      (node (ref "Q") (pin "3") (pinfunction "E_3") (pintype "passive"))
    )
    (net (code "66") (name "Net-(Q-S)") (class "Default")
      (node (ref "C7") (pin "-") (pinfunction "-_-") (pintype "passive"))
      (node (ref "Q") (pin "2") (pinfunction "S_2") (pintype "passive"))
    )
    (net (code "67") (name "Net-(Q1-B)") (class "Default")
      (node (ref "Q1") (pin "1") (pinfunction "B_1") (pintype "passive"))
      (node (ref "Q4") (pin "1") (pinfunction "B_1") (pintype "passive"))
      (node (ref "R4") (pin "1") (pinfunction "1_1") (pintype "passive"))
      (node (ref "R49") (pin "2") (pinfunction "2_2") (pintype "passive"))
    )
    (net (code "68") (name "Net-(Q2-B)") (class "Default")
      (node (ref "Q2") (pin "1") (pinfunction "B_1") (pintype "passive"))
      (node (ref "Q5") (pin "1") (pinfunction "B_1") (pintype "passive"))
      (node (ref "R3") (pin "1") (pinfunction "1_1") (pintype "passive"))
      (node (ref "R4") (pin "2") (pinfunction "2_2") (pintype "passive"))
    )
    (net (code "69") (name "Net-(Q3-B)") (class "Default")
      (node (ref "Q3") (pin "1") (pinfunction "B_1") (pintype "passive"))
      (node (ref "Q6") (pin "1") (pinfunction "B_1") (pintype "passive"))
      (node (ref "R2") (pin "1") (pinfunction "1_1") (pintype "passive"))
      (node (ref "R3") (pin "2") (pinfunction "2_2") (pintype "passive"))
    )
    (net (code "70") (name "Net-(Q7-B)") (class "Default")
      (node (ref "MIN") (pin "P$3") (pinfunction "P$3_P$3") (pintype "bidirectional"))
      (node (ref "Q7") (pin "1") (pinfunction "B_1") (pintype "passive"))
      (node (ref "R43") (pin "2") (pinfunction "2_2") (pintype "passive"))
    )
    (net (code "71") (name "Net-(SCALE-PadE)") (class "Default")
      (node (ref "SCALE") (pin "E") (pinfunction "E_E") (pintype "passive"))
      (node (ref "VPEROCT") (pin "P$3") (pinfunction "P$3_P$3") (pintype "bidirectional"))
    )
    (net (code "72") (name "Net-(U$1A-B)") (class "Default")
      (node (ref "R10") (pin "2") (pinfunction "2_2") (pintype "passive"))
      (node (ref "R5") (pin "1") (pinfunction "1_1") (pintype "passive"))
      (node (ref "U$1") (pin "2") (pinfunction "B_2") (pintype "passive"))
    )
    (net (code "73") (name "Net-(U$1A-E)") (class "Default")
      (node (ref "U$1") (pin "1") (pinfunction "E_1") (pintype "passive"))
      (node (ref "U$1") (pin "4") (pinfunction "E_4") (pintype "passive"))
      (node (ref "U$3") (pin "3") (pinfunction "C_3") (pintype "passive"))
    )
    (net (code "74") (name "Net-(U$1B-B)") (class "Default")
      (node (ref "R11") (pin "1") (pinfunction "1_1") (pintype "passive"))
      (node (ref "R16") (pin "1") (pinfunction "1_1") (pintype "passive"))
      (node (ref "U$1") (pin "5") (pinfunction "B_5") (pintype "passive"))
    )
    (net (code "75") (name "Net-(U$2A-B)") (class "Default")
      (node (ref "R1") (pin "1") (pinfunction "1_1") (pintype "passive"))
      (node (ref "R2") (pin "2") (pinfunction "2_2") (pintype "passive"))
      (node (ref "U$2") (pin "2") (pinfunction "B_2") (pintype "passive"))
      (node (ref "U$2") (pin "5") (pinfunction "B_5") (pintype "passive"))
    )
    (net (code "76") (name "Net-(U$3A-B)") (class "Default")
      (node (ref "R22") (pin "2") (pinfunction "2_2") (pintype "passive"))
      (node (ref "R23") (pin "2") (pinfunction "2_2") (pintype "passive"))
      (node (ref "U$3") (pin "2") (pinfunction "B_2") (pintype "passive"))
    )
    (net (code "77") (name "Net-(U$3A-E)") (class "Default")
      (node (ref "R7") (pin "2") (pinfunction "2_2") (pintype "passive"))
      (node (ref "U$3") (pin "1") (pinfunction "E_1") (pintype "passive"))
      (node (ref "U$3") (pin "4") (pinfunction "E_4") (pintype "passive"))
    )
    (net (code "78") (name "unconnected-(POWERC-KL-Pad11)") (class "Default")
      (node (ref "POWER") (pin "11") (pinfunction "KL_11") (pintype "passive"))
    )
    (net (code "79") (name "unconnected-(POWERD-KL-Pad12)") (class "Default")
      (node (ref "POWER") (pin "12") (pinfunction "KL_12") (pintype "passive"))
    )
    (net (code "80") (name "unconnected-(POWERE-KL-Pad13)") (class "Default")
      (node (ref "POWER") (pin "13") (pinfunction "KL_13") (pintype "passive"))
    )
    (net (code "81") (name "unconnected-(POWERF-KL-Pad14)") (class "Default")
      (node (ref "POWER") (pin "14") (pinfunction "KL_14") (pintype "passive"))
    )
    (net (code "82") (name "unconnected-(POWERG-KL-Pad15)") (class "Default")
      (node (ref "POWER") (pin "15") (pinfunction "KL_15") (pintype "passive"))
    )
    (net (code "83") (name "unconnected-(POWERH-KL-Pad16)") (class "Default")
      (node (ref "POWER") (pin "16") (pinfunction "KL_16") (pintype "passive"))
    )
  )
)
